# DFN-8.net
KiCad netlist of a schematic drawn in EAGLE
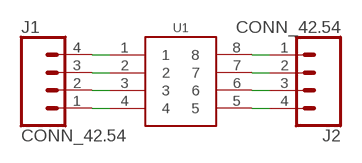
[diagram p0: schematic, sheet 1]

(export (version "E")
  (design (tool "Eeschema 10.0.6"))
  (components
    (comp (ref "J1")
      (value "CONN_42.54")
      (footprint "eagle-import:1X04")
      (libsource (lib "eagle-import") (part "CONN_42.54"))
    )
    (comp (ref "J2")
      (value "CONN_42.54")
      (footprint "eagle-import:1X04")
      (libsource (lib "eagle-import") (part "CONN_42.54"))
    )
    (comp (ref "U1")
      (value "GEN_8DFN")
      (footprint "eagle-import:DFN_8_2.5X2.5")
      (libsource (lib "eagle-import") (part "GEN_8DFN"))
    )
  )
  (nets
    (net (code "1") (name "Net-(J1-Pad1)") (class "Default")
      (node (ref "J1") (pin "1") (pinfunction "1_1") (pintype "passive"))
      (node (ref "U1") (pin "4") (pinfunction "4_4") (pintype "bidirectional"))
    )
    (net (code "2") (name "Net-(J1-Pad2)") (class "Default")
      (node (ref "J1") (pin "2") (pinfunction "2_2") (pintype "passive"))
      (node (ref "U1") (pin "3") (pinfunction "3_3") (pintype "bidirectional"))
    )
    (net (code "3") (name "Net-(J1-Pad3)") (class "Default")
      (node (ref "J1") (pin "3") (pinfunction "3_3") (pintype "passive"))
      (node (ref "U1") (pin "2") (pinfunction "2_2") (pintype "bidirectional"))
    )
    (net (code "4") (name "Net-(J1-Pad4)") (class "Default")
      (node (ref "J1") (pin "4") (pinfunction "4_4") (pintype "passive"))
      (node (ref "U1") (pin "1") (pinfunction "1_1") (pintype "bidirectional"))
    )
    (net (code "5") (name "Net-(J2-Pad1)") (class "Default")
      (node (ref "J2") (pin "1") (pinfunction "1_1") (pintype "passive"))
      (node (ref "U1") (pin "8") (pinfunction "8_8") (pintype "bidirectional"))
    )
    (net (code "6") (name "Net-(J2-Pad2)") (class "Default")
      (node (ref "J2") (pin "2") (pinfunction "2_2") (pintype "passive"))
      (node (ref "U1") (pin "7") (pinfunction "7_7") (pintype "bidirectional"))
    )
    (net (code "7") (name "Net-(J2-Pad3)") (class "Default")
      (node (ref "J2") (pin "3") (pinfunction "3_3") (pintype "passive"))
      (node (ref "U1") (pin "6") (pinfunction "6_6") (pintype "bidirectional"))
    )
    (net (code "8") (name "Net-(J2-Pad4)") (class "Default")
      (node (ref "J2") (pin "4") (pinfunction "4_4") (pintype "passive"))
      (node (ref "U1") (pin "5") (pinfunction "5_5") (pintype "bidirectional"))
    )
  )
)
